# 8_Emulator_Interface.net
KiCad netlist of a schematic drawn in Altium Designer
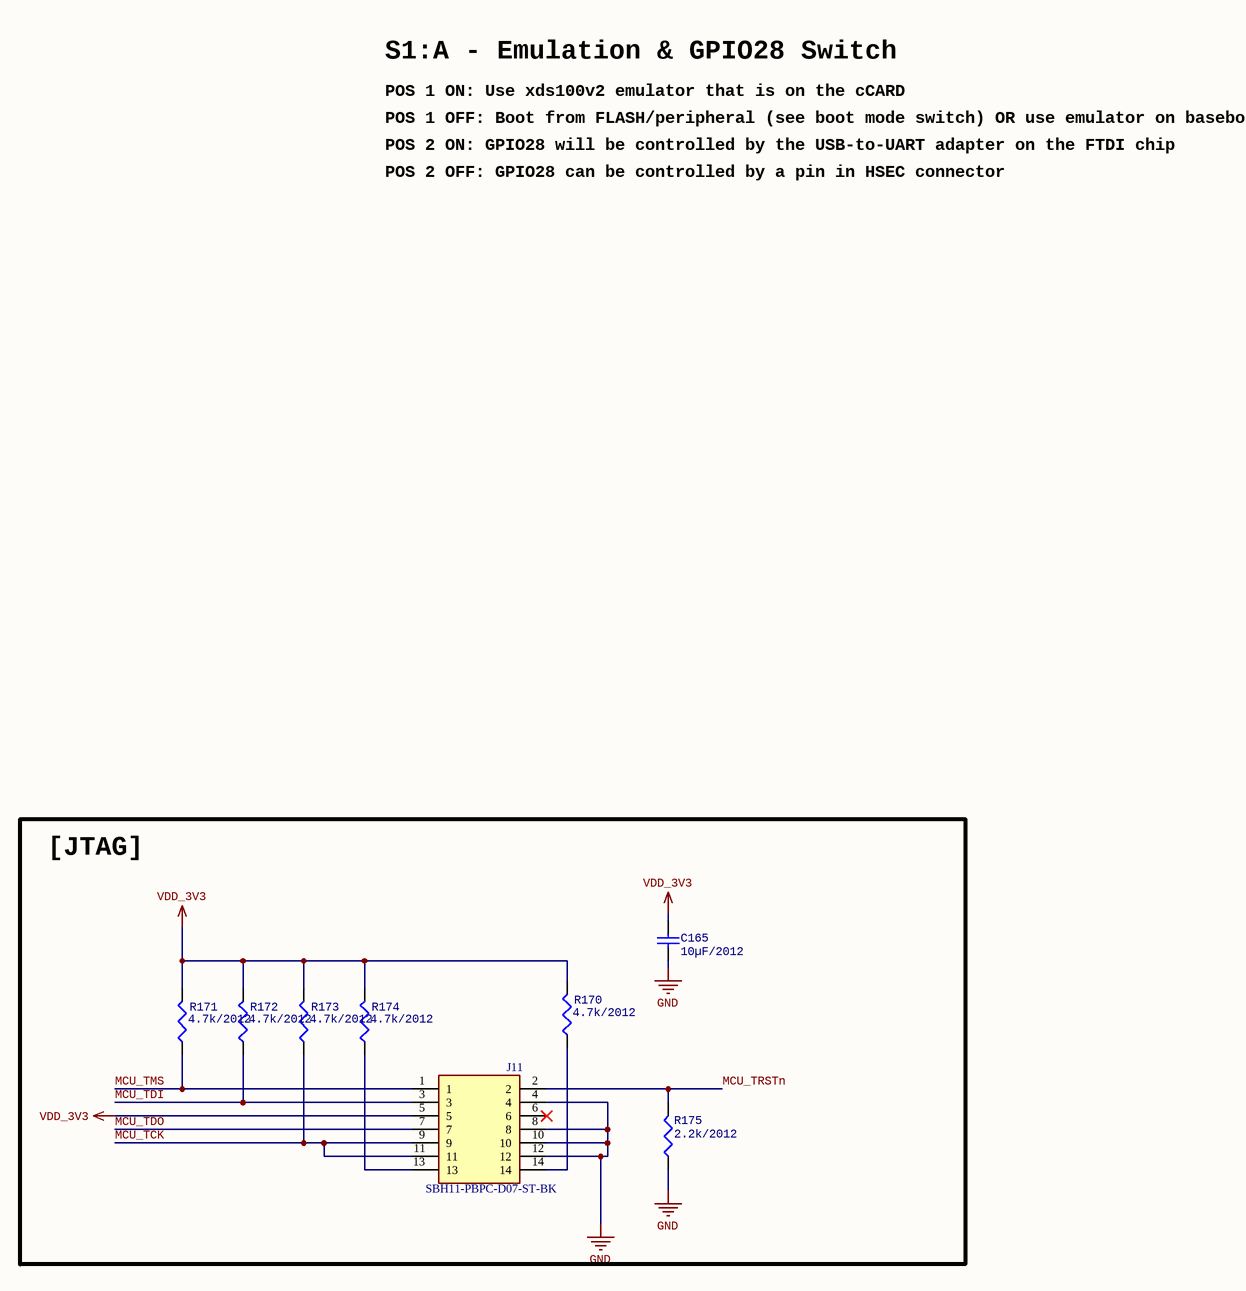
[diagram p0: 8.Emulator_Interface.SchDoc]

(export (version "E")
  (design (tool "Eeschema 10.0.6"))
  (components
    (comp (ref "C165")
      (value "10µF/2012")
      (footprint "CAPC2013X135X45NL10T25")
      (description "Chip Capacitor, 1 uF, +/- 10%, 50 V, 0805 (2012 Metric)")
      (fields (field (name "TOLERANCE") "10%") (field (name "Comment") "C2012"))
      (libsource (lib "PEETS_V2") (part "CAP-NP-2"))
    )
    (comp (ref "J11")
      (value "SBH11-PBPC-D07-ST-BK")
      (footprint "SULLINS_SBH11-PBPC-D07-ST-BK")
      (description "Connector Header Through Hole 14 position 0.100 (2.54mm)")
      (fields (field (name "MF") "Sullins Connector"))
      (libsource (lib "PEETS_V2") (part "SBH11-PBPC-D07-ST-BK"))
    )
    (comp (ref "R170")
      (value "4.7k/2012")
      (footprint "RESC0805(2012)_L")
      (description "Chip Resistor, 4,7 Ohms, +/-5 %, 125 mW, -55 to 155 degC, 0805")
      (fields (field (name "POWER") "125mW") (field (name "TOLERANCE") "5%"))
      (libsource (lib "PEETS_V2") (part "RES-2"))
    )
    (comp (ref "R171")
      (value "4.7k/2012")
      (footprint "RESC0805(2012)_L")
      (description "Chip Resistor, 4,7 Ohms, +/-5 %, 125 mW, -55 to 155 degC, 0805")
      (fields (field (name "POWER") "125mW") (field (name "TOLERANCE") "5%"))
      (libsource (lib "PEETS_V2") (part "RES-2"))
    )
    (comp (ref "R172")
      (value "4.7k/2012")
      (footprint "RESC0805(2012)_L")
      (description "Chip Resistor, 4,7 Ohms, +/-5 %, 125 mW, -55 to 155 degC, 0805")
      (fields (field (name "POWER") "125mW") (field (name "TOLERANCE") "5%"))
      (libsource (lib "PEETS_V2") (part "RES-2"))
    )
    (comp (ref "R173")
      (value "4.7k/2012")
      (footprint "RESC0805(2012)_L")
      (description "Chip Resistor, 4,7 Ohms, +/-5 %, 125 mW, -55 to 155 degC, 0805")
      (fields (field (name "POWER") "125mW") (field (name "TOLERANCE") "5%"))
      (libsource (lib "PEETS_V2") (part "RES-2"))
    )
    (comp (ref "R174")
      (value "4.7k/2012")
      (footprint "RESC0805(2012)_L")
      (description "Chip Resistor, 4,7 Ohms, +/-5 %, 125 mW, -55 to 155 degC, 0805")
      (fields (field (name "POWER") "125mW") (field (name "TOLERANCE") "5%"))
      (libsource (lib "PEETS_V2") (part "RES-2"))
    )
    (comp (ref "R175")
      (value "2.2k/2012")
      (footprint "RESC0805(2012)_L")
      (description "Chip Resistor, 4,7 Ohms, +/-5 %, 125 mW, -55 to 155 degC, 0805")
      (fields (field (name "POWER") "125mW") (field (name "TOLERANCE") "5%"))
      (libsource (lib "PEETS_V2") (part "RES-2"))
    )
  )
  (nets
    (net (code "1") (name "/MCU_TCK") (class "Default")
      (node (ref "J11") (pin "11") (pinfunction "11_11") (pintype "passive"))
      (node (ref "J11") (pin "9") (pinfunction "9_9") (pintype "passive"))
      (node (ref "R173") (pin "1") (pinfunction "1_1") (pintype "passive"))
    )
    (net (code "2") (name "/MCU_TDI") (class "Default")
      (node (ref "J11") (pin "3") (pinfunction "3_3") (pintype "passive"))
      (node (ref "R172") (pin "1") (pinfunction "1_1") (pintype "passive"))
    )
    (net (code "3") (name "/MCU_TDO") (class "Default")
      (node (ref "J11") (pin "7") (pinfunction "7_7") (pintype "passive"))
    )
    (net (code "4") (name "/MCU_TMS") (class "Default")
      (node (ref "J11") (pin "1") (pinfunction "1_1") (pintype "passive"))
      (node (ref "R171") (pin "1") (pinfunction "1_1") (pintype "passive"))
    )
    (net (code "5") (name "/MCU_TRSTn") (class "Default")
      (node (ref "J11") (pin "2") (pinfunction "2_2") (pintype "passive"))
      (node (ref "R175") (pin "2") (pinfunction "2_2") (pintype "passive"))
    )
    (net (code "6") (name "GND") (class "Default")
      (node (ref "C165") (pin "2") (pinfunction "2_2") (pintype "passive"))
      (node (ref "J11") (pin "10") (pinfunction "10_10") (pintype "passive"))
      (node (ref "J11") (pin "12") (pinfunction "12_12") (pintype "passive"))
      (node (ref "J11") (pin "4") (pinfunction "4_4") (pintype "passive"))
      (node (ref "J11") (pin "8") (pinfunction "8_8") (pintype "passive"))
      (node (ref "R175") (pin "1") (pinfunction "1_1") (pintype "passive"))
    )
    (net (code "7") (name "Net-(J11-Pad13)") (class "Default")
      (node (ref "J11") (pin "13") (pinfunction "13_13") (pintype "passive"))
      (node (ref "R174") (pin "1") (pinfunction "1_1") (pintype "passive"))
    )
    (net (code "8") (name "Net-(J11-Pad14)") (class "Default")
      (node (ref "J11") (pin "14") (pinfunction "14_14") (pintype "passive"))
      (node (ref "R170") (pin "1") (pinfunction "1_1") (pintype "passive"))
    )
    (net (code "9") (name "VDD_3V3") (class "Default")
      (node (ref "C165") (pin "1") (pinfunction "1_1") (pintype "passive"))
      (node (ref "J11") (pin "5") (pinfunction "5_5") (pintype "passive"))
      (node (ref "R170") (pin "2") (pinfunction "2_2") (pintype "passive"))
      (node (ref "R171") (pin "2") (pinfunction "2_2") (pintype "passive"))
      (node (ref "R172") (pin "2") (pinfunction "2_2") (pintype "passive"))
      (node (ref "R173") (pin "2") (pinfunction "2_2") (pintype "passive"))
      (node (ref "R174") (pin "2") (pinfunction "2_2") (pintype "passive"))
    )
    (net (code "10") (name "unconnected-(J11-Pad6)") (class "Default")
      (node (ref "J11") (pin "6") (pinfunction "6_6") (pintype "passive+no_connect"))
    )
  )
)
